# particle-logo-v2.net
KiCad netlist of a schematic drawn in EAGLE
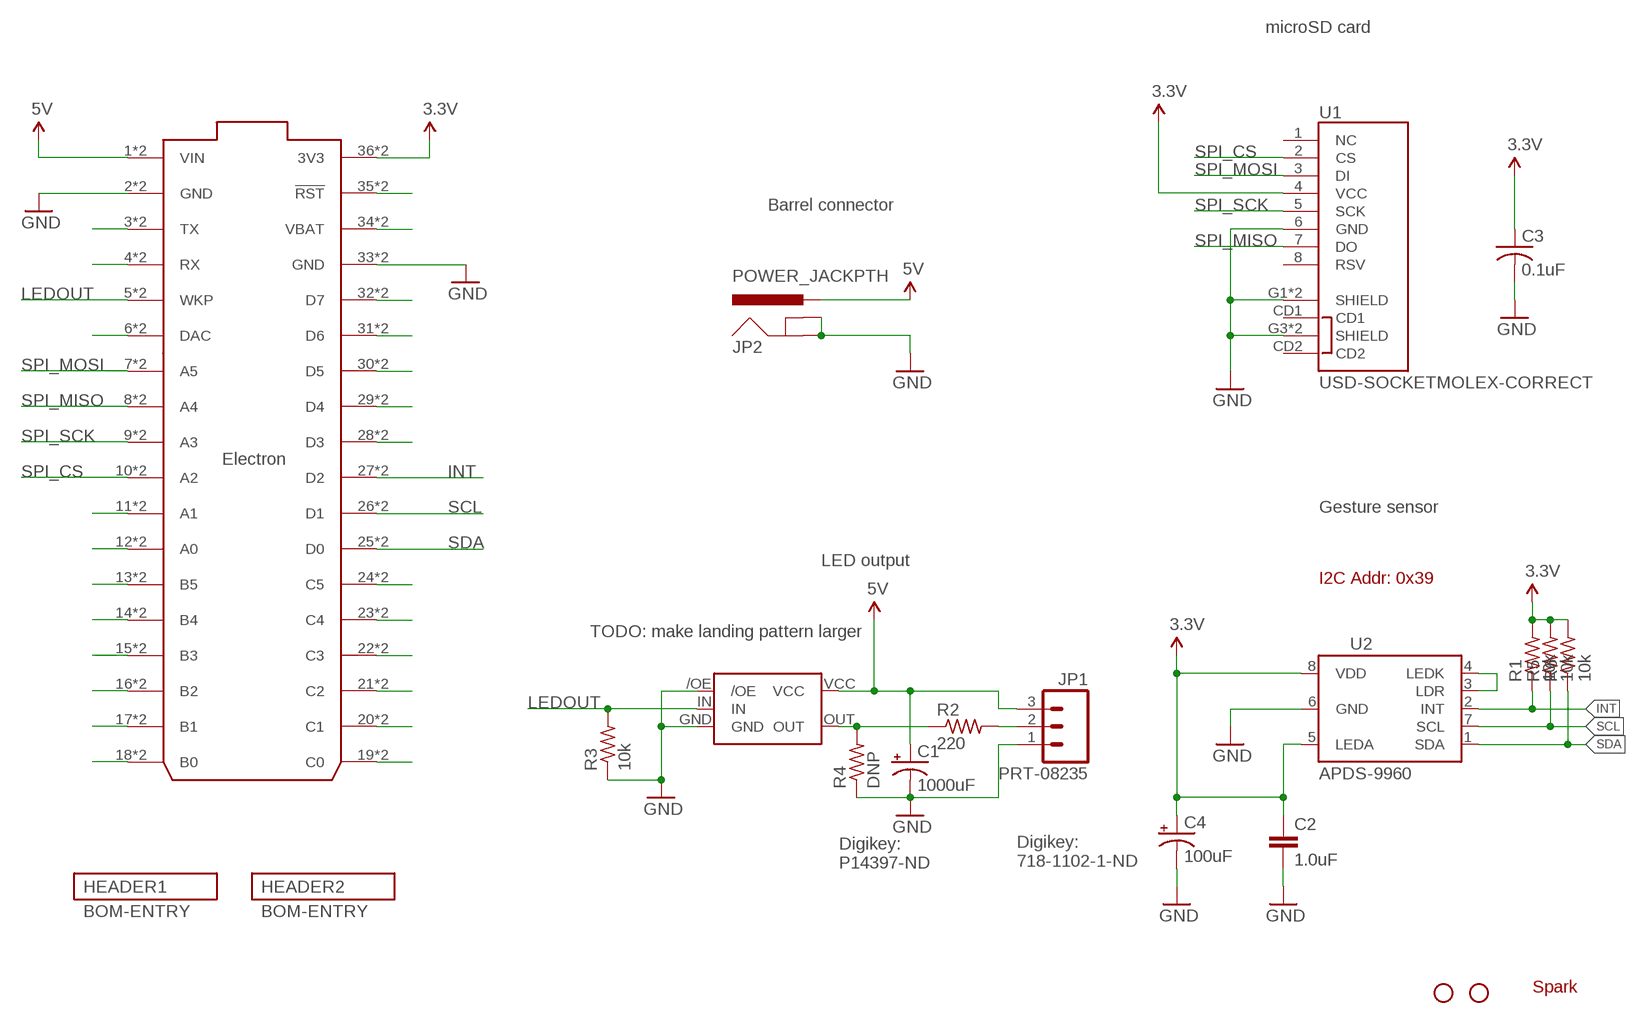
[diagram p0: schematic, sheet 1]

(export (version "E")
  (design (tool "Eeschema 10.0.6"))
  (components
    (comp (ref "C1")
      (value "1000uF")
      (footprint "eagle-import:CPOL-8MMX20MM-FLAT-MIR")
      (fields (field (name "PARTNO") "EEU-FR1C102L"))
      (libsource (lib "eagle-import") (part "CAP_POL8MMX20MM-FLAT-MIR"))
    )
    (comp (ref "C2")
      (value "1.0uF")
      (footprint "eagle-import:0603-CAP")
      (fields (field (name "PARTNO") "0603YD105KAT2A"))
      (libsource (lib "eagle-import") (part "1.0UF-16V-10%(0603)"))
    )
    (comp (ref "C3")
      (value "0.1uF")
      (footprint "eagle-import:C0603")
      (fields (field (name "PARTNO") "CC0603JRX7R7BB104"))
      (libsource (lib "eagle-import") (part "C-USC0603"))
    )
    (comp (ref "C4")
      (value "100uF")
      (footprint "eagle-import:EIA7343")
      (fields (field (name "PARTNO") "TAJD107K020RNJ"))
      (libsource (lib "eagle-import") (part "100UF-10V-10%(TANT)"))
    )
    (comp (ref "JP1")
      (value "PRT-08235")
      (footprint "eagle-import:SCREWTERMINAL-3.5MM-3")
      (libsource (lib "eagle-import") (part "M03SCREW"))
    )
    (comp (ref "JP2")
      (value "POWER_JACKPTH")
      (footprint "eagle-import:POWER_JACK_PTH")
      (libsource (lib "eagle-import") (part "POWER_JACKPTH"))
    )
    (comp (ref "R1")
      (value "10k")
      (footprint "eagle-import:R0603")
      (fields (field (name "PARTNO") "ERJ-3EKF1002V"))
      (libsource (lib "eagle-import") (part "R-US_R0603"))
    )
    (comp (ref "R2")
      (value "220")
      (footprint "eagle-import:R0603")
      (fields (field (name "PARTNO") "ERJ-3GEYJ221V"))
      (libsource (lib "eagle-import") (part "R-US_R0603"))
    )
    (comp (ref "R3")
      (value "10k")
      (footprint "eagle-import:R0603")
      (fields (field (name "PARTNO") "ERJ-3EKF1002V"))
      (libsource (lib "eagle-import") (part "R-US_R0603"))
    )
    (comp (ref "R4")
      (value "DNP")
      (footprint "eagle-import:R0603")
      (libsource (lib "eagle-import") (part "R-US_R0603"))
    )
    (comp (ref "R5")
      (value "10k")
      (footprint "eagle-import:R0603")
      (fields (field (name "PARTNO") "ERJ-3EKF1002V"))
      (libsource (lib "eagle-import") (part "R-US_R0603"))
    )
    (comp (ref "R6")
      (value "10k")
      (footprint "eagle-import:R0603")
      (fields (field (name "PARTNO") "ERJ-3EKF1002V"))
      (libsource (lib "eagle-import") (part "R-US_R0603"))
    )
    (comp (ref "STANDOFF1")
      (value "STAND-OFF")
      (footprint "eagle-import:STAND-OFF")
      (libsource (lib "eagle-import") (part "STAND-OFF"))
    )
    (comp (ref "STANDOFF2")
      (value "STAND-OFF")
      (footprint "eagle-import:STAND-OFF")
      (libsource (lib "eagle-import") (part "STAND-OFF"))
    )
    (comp (ref "U$1")
      (value "SPARK_LOGO2")
      (footprint "eagle-import:SPARK_LOGO2")
      (libsource (lib "eagle-import") (part "SPARK_LOGO2"))
    )
    (comp (ref "U1")
      (value "USD-SOCKETMOLEX-CORRECT")
      (footprint "eagle-import:MICRO-SD-MOLEX-CORRECT")
      (fields (field (name "PARTNO") "1040310811"))
      (libsource (lib "eagle-import") (part "USD-SOCKETMOLEX-CORRECT"))
    )
    (comp (ref "U2")
      (value "APDS-9960")
      (footprint "eagle-import:APDS-9960")
      (libsource (lib "eagle-import") (part "APDS-9960"))
    )
    (comp (ref "U3")
      (value "ELECTRON_WITH_EXTERNAL_HEADERS_NT")
      (footprint "eagle-import:ELECTRON_EXTERNAL_NT")
      (libsource (lib "eagle-import") (part "ELECTRON_WITH_EXTERNAL_HEADERS_NT"))
    )
    (comp (ref "U4")
      (value "NL17SZ125SOT553")
      (footprint "eagle-import:SOT-553")
      (fields (field (name "PARTNO") "NL17SZ125DTT1G"))
      (libsource (lib "eagle-import") (part "NL17SZ125SOT553"))
    )
  )
  (nets
    (net (code "1") (name "/LEDOUT") (class "Default")
      (node (ref "R3") (pin "2") (pinfunction "2_2") (pintype "passive"))
      (node (ref "U3") (pin "5") (pinfunction "WKP_5") (pintype "bidirectional"))
      (node (ref "U3") (pin "@5") (pinfunction "WKP_@5") (pintype "bidirectional"))
      (node (ref "U4") (pin "IN") (pinfunction "IN_IN") (pintype "bidirectional"))
    )
    (net (code "2") (name "/SPI_CS") (class "Default")
      (node (ref "U1") (pin "2") (pinfunction "CS_2") (pintype "bidirectional"))
      (node (ref "U3") (pin "10") (pinfunction "A2_10") (pintype "bidirectional"))
      (node (ref "U3") (pin "@10") (pinfunction "A2_@10") (pintype "bidirectional"))
    )
    (net (code "3") (name "/SPI_MISO") (class "Default")
      (node (ref "U1") (pin "7") (pinfunction "DO_7") (pintype "bidirectional"))
      (node (ref "U3") (pin "8") (pinfunction "A4_8") (pintype "bidirectional"))
      (node (ref "U3") (pin "@8") (pinfunction "A4_@8") (pintype "bidirectional"))
    )
    (net (code "4") (name "/SPI_MOSI") (class "Default")
      (node (ref "U1") (pin "3") (pinfunction "DI_3") (pintype "bidirectional"))
      (node (ref "U3") (pin "7") (pinfunction "A5_7") (pintype "bidirectional"))
      (node (ref "U3") (pin "@7") (pinfunction "A5_@7") (pintype "bidirectional"))
    )
    (net (code "5") (name "/SPI_SCK") (class "Default")
      (node (ref "U1") (pin "5") (pinfunction "SCK_5") (pintype "bidirectional"))
      (node (ref "U3") (pin "9") (pinfunction "A3_9") (pintype "bidirectional"))
      (node (ref "U3") (pin "@9") (pinfunction "A3_@9") (pintype "bidirectional"))
    )
    (net (code "6") (name "3.3V") (class "Default")
      (node (ref "C2") (pin "1") (pinfunction "1_1") (pintype "passive"))
      (node (ref "C3") (pin "1") (pinfunction "1_1") (pintype "passive"))
      (node (ref "C4") (pin "A") (pinfunction "+_A") (pintype "passive"))
      (node (ref "R1") (pin "2") (pinfunction "2_2") (pintype "passive"))
      (node (ref "R5") (pin "2") (pinfunction "2_2") (pintype "passive"))
      (node (ref "R6") (pin "2") (pinfunction "2_2") (pintype "passive"))
      (node (ref "U1") (pin "4") (pinfunction "VCC_4") (pintype "bidirectional"))
      (node (ref "U2") (pin "5") (pinfunction "LEDA_5") (pintype "bidirectional"))
      (node (ref "U2") (pin "8") (pinfunction "VDD_8") (pintype "bidirectional"))
      (node (ref "U3") (pin "36") (pinfunction "3V3_36") (pintype "power_in"))
      (node (ref "U3") (pin "@36") (pinfunction "3V3_@36") (pintype "power_in"))
    )
    (net (code "7") (name "5V") (class "Default")
      (node (ref "C1") (pin "2") (pinfunction "+_2") (pintype "passive"))
      (node (ref "JP1") (pin "3") (pinfunction "3_3") (pintype "passive"))
      (node (ref "JP2") (pin "PWR") (pinfunction "PWR_PWR") (pintype "bidirectional"))
      (node (ref "U3") (pin "1") (pinfunction "VIN_1") (pintype "power_in"))
      (node (ref "U3") (pin "@1") (pinfunction "VIN_@1") (pintype "power_in"))
      (node (ref "U4") (pin "VCC") (pinfunction "VCC_VCC") (pintype "bidirectional"))
    )
    (net (code "8") (name "GND") (class "Default")
      (node (ref "C1") (pin "1") (pinfunction "-_1") (pintype "passive"))
      (node (ref "C2") (pin "2") (pinfunction "2_2") (pintype "passive"))
      (node (ref "C3") (pin "2") (pinfunction "2_2") (pintype "passive"))
      (node (ref "C4") (pin "C") (pinfunction "-_C") (pintype "passive"))
      (node (ref "JP1") (pin "1") (pinfunction "1_1") (pintype "passive"))
      (node (ref "JP2") (pin "GND") (pinfunction "GND_GND") (pintype "bidirectional"))
      (node (ref "JP2") (pin "GNDBREAK") (pinfunction "GNDBREAK_GNDBREAK") (pintype "bidirectional"))
      (node (ref "R3") (pin "1") (pinfunction "1_1") (pintype "passive"))
      (node (ref "R4") (pin "1") (pinfunction "1_1") (pintype "passive"))
      (node (ref "U1") (pin "6") (pinfunction "GND_6") (pintype "bidirectional"))
      (node (ref "U1") (pin "G1") (pinfunction "SHIELD_G1") (pintype "bidirectional"))
      (node (ref "U1") (pin "G2") (pinfunction "SHIELD_G2") (pintype "bidirectional"))
      (node (ref "U1") (pin "G3") (pinfunction "SHIELD_G3") (pintype "bidirectional"))
      (node (ref "U1") (pin "G4") (pinfunction "SHIELD_G4") (pintype "bidirectional"))
      (node (ref "U2") (pin "6") (pinfunction "GND_6") (pintype "bidirectional"))
      (node (ref "U3") (pin "2") (pinfunction "GND_2") (pintype "power_in"))
      (node (ref "U3") (pin "33") (pinfunction "GND_33") (pintype "power_in"))
      (node (ref "U3") (pin "@2") (pinfunction "GND_@2") (pintype "power_in"))
      (node (ref "U3") (pin "@33") (pinfunction "GND_@33") (pintype "power_in"))
      (node (ref "U4") (pin "/OE") (pinfunction "/OE_/OE") (pintype "bidirectional"))
      (node (ref "U4") (pin "GND") (pinfunction "GND_GND") (pintype "bidirectional"))
    )
    (net (code "9") (name "INT") (class "Default")
      (node (ref "R1") (pin "1") (pinfunction "1_1") (pintype "passive"))
      (node (ref "U2") (pin "2") (pinfunction "INT_2") (pintype "bidirectional"))
      (node (ref "U3") (pin "27") (pinfunction "D2_27") (pintype "bidirectional"))
      (node (ref "U3") (pin "@27") (pinfunction "D2_@27") (pintype "bidirectional"))
    )
    (net (code "10") (name "Net-(JP1-Pad2)") (class "Default")
      (node (ref "JP1") (pin "2") (pinfunction "2_2") (pintype "passive"))
      (node (ref "R2") (pin "2") (pinfunction "2_2") (pintype "passive"))
    )
    (net (code "11") (name "Net-(R2-Pad1)") (class "Default")
      (node (ref "R2") (pin "1") (pinfunction "1_1") (pintype "passive"))
      (node (ref "R4") (pin "2") (pinfunction "2_2") (pintype "passive"))
      (node (ref "U4") (pin "OUT") (pinfunction "OUT_OUT") (pintype "bidirectional"))
    )
    (net (code "12") (name "Net-(U2-LDR)") (class "Default")
      (node (ref "U2") (pin "3") (pinfunction "LDR_3") (pintype "bidirectional"))
      (node (ref "U2") (pin "4") (pinfunction "LEDK_4") (pintype "bidirectional"))
    )
    (net (code "13") (name "Net-(U3-A0-Pad12)") (class "Default")
      (node (ref "U3") (pin "12") (pinfunction "A0_12") (pintype "bidirectional"))
      (node (ref "U3") (pin "@12") (pinfunction "A0_@12") (pintype "bidirectional"))
    )
    (net (code "14") (name "Net-(U3-A1-Pad11)") (class "Default")
      (node (ref "U3") (pin "11") (pinfunction "A1_11") (pintype "bidirectional"))
      (node (ref "U3") (pin "@11") (pinfunction "A1_@11") (pintype "bidirectional"))
    )
    (net (code "15") (name "Net-(U3-B0-Pad18)") (class "Default")
      (node (ref "U3") (pin "18") (pinfunction "B0_18") (pintype "bidirectional"))
      (node (ref "U3") (pin "@18") (pinfunction "B0_@18") (pintype "bidirectional"))
    )
    (net (code "16") (name "Net-(U3-B1-Pad17)") (class "Default")
      (node (ref "U3") (pin "17") (pinfunction "B1_17") (pintype "bidirectional"))
      (node (ref "U3") (pin "@17") (pinfunction "B1_@17") (pintype "bidirectional"))
    )
    (net (code "17") (name "Net-(U3-B2-Pad16)") (class "Default")
      (node (ref "U3") (pin "16") (pinfunction "B2_16") (pintype "bidirectional"))
      (node (ref "U3") (pin "@16") (pinfunction "B2_@16") (pintype "bidirectional"))
    )
    (net (code "18") (name "Net-(U3-B3-Pad15)") (class "Default")
      (node (ref "U3") (pin "15") (pinfunction "B3_15") (pintype "bidirectional"))
      (node (ref "U3") (pin "@15") (pinfunction "B3_@15") (pintype "bidirectional"))
    )
    (net (code "19") (name "Net-(U3-B4-Pad14)") (class "Default")
      (node (ref "U3") (pin "14") (pinfunction "B4_14") (pintype "bidirectional"))
      (node (ref "U3") (pin "@14") (pinfunction "B4_@14") (pintype "bidirectional"))
    )
    (net (code "20") (name "Net-(U3-B5-Pad13)") (class "Default")
      (node (ref "U3") (pin "13") (pinfunction "B5_13") (pintype "bidirectional"))
      (node (ref "U3") (pin "@13") (pinfunction "B5_@13") (pintype "bidirectional"))
    )
    (net (code "21") (name "Net-(U3-C0-Pad19)") (class "Default")
      (node (ref "U3") (pin "19") (pinfunction "C0_19") (pintype "bidirectional"))
      (node (ref "U3") (pin "@19") (pinfunction "C0_@19") (pintype "bidirectional"))
    )
    (net (code "22") (name "Net-(U3-C1-Pad20)") (class "Default")
      (node (ref "U3") (pin "20") (pinfunction "C1_20") (pintype "bidirectional"))
      (node (ref "U3") (pin "@20") (pinfunction "C1_@20") (pintype "bidirectional"))
    )
    (net (code "23") (name "Net-(U3-C2-Pad21)") (class "Default")
      (node (ref "U3") (pin "21") (pinfunction "C2_21") (pintype "bidirectional"))
      (node (ref "U3") (pin "@21") (pinfunction "C2_@21") (pintype "bidirectional"))
    )
    (net (code "24") (name "Net-(U3-C3-Pad22)") (class "Default")
      (node (ref "U3") (pin "22") (pinfunction "C3_22") (pintype "bidirectional"))
      (node (ref "U3") (pin "@22") (pinfunction "C3_@22") (pintype "bidirectional"))
    )
    (net (code "25") (name "Net-(U3-C4-Pad23)") (class "Default")
      (node (ref "U3") (pin "23") (pinfunction "C4_23") (pintype "bidirectional"))
      (node (ref "U3") (pin "@23") (pinfunction "C4_@23") (pintype "bidirectional"))
    )
    (net (code "26") (name "Net-(U3-C5-Pad24)") (class "Default")
      (node (ref "U3") (pin "24") (pinfunction "C5_24") (pintype "bidirectional"))
      (node (ref "U3") (pin "@24") (pinfunction "C5_@24") (pintype "bidirectional"))
    )
    (net (code "27") (name "Net-(U3-D3-Pad28)") (class "Default")
      (node (ref "U3") (pin "28") (pinfunction "D3_28") (pintype "bidirectional"))
      (node (ref "U3") (pin "@28") (pinfunction "D3_@28") (pintype "bidirectional"))
    )
    (net (code "28") (name "Net-(U3-D4-Pad29)") (class "Default")
      (node (ref "U3") (pin "29") (pinfunction "D4_29") (pintype "bidirectional"))
      (node (ref "U3") (pin "@29") (pinfunction "D4_@29") (pintype "bidirectional"))
    )
    (net (code "29") (name "Net-(U3-D5-Pad30)") (class "Default")
      (node (ref "U3") (pin "30") (pinfunction "D5_30") (pintype "bidirectional"))
      (node (ref "U3") (pin "@30") (pinfunction "D5_@30") (pintype "bidirectional"))
    )
    (net (code "30") (name "Net-(U3-D6-Pad31)") (class "Default")
      (node (ref "U3") (pin "31") (pinfunction "D6_31") (pintype "bidirectional"))
      (node (ref "U3") (pin "@31") (pinfunction "D6_@31") (pintype "bidirectional"))
    )
    (net (code "31") (name "Net-(U3-D7-Pad32)") (class "Default")
      (node (ref "U3") (pin "32") (pinfunction "D7_32") (pintype "bidirectional"))
      (node (ref "U3") (pin "@32") (pinfunction "D7_@32") (pintype "bidirectional"))
    )
    (net (code "32") (name "Net-(U3-DAC-Pad6)") (class "Default")
      (node (ref "U3") (pin "6") (pinfunction "DAC_6") (pintype "bidirectional"))
      (node (ref "U3") (pin "@6") (pinfunction "DAC_@6") (pintype "bidirectional"))
    )
    (net (code "33") (name "Net-(U3-RX-Pad4)") (class "Default")
      (node (ref "U3") (pin "4") (pinfunction "RX_4") (pintype "bidirectional"))
      (node (ref "U3") (pin "@4") (pinfunction "RX_@4") (pintype "bidirectional"))
    )
    (net (code "34") (name "Net-(U3-TX-Pad3)") (class "Default")
      (node (ref "U3") (pin "3") (pinfunction "TX_3") (pintype "bidirectional"))
      (node (ref "U3") (pin "@3") (pinfunction "TX_@3") (pintype "bidirectional"))
    )
    (net (code "35") (name "Net-(U3-VBAT-Pad34)") (class "Default")
      (node (ref "U3") (pin "34") (pinfunction "VBAT_34") (pintype "power_in"))
      (node (ref "U3") (pin "@34") (pinfunction "VBAT_@34") (pintype "power_in"))
    )
    (net (code "36") (name "Net-(U3-~{RST}-Pad35)") (class "Default")
      (node (ref "U3") (pin "35") (pinfunction "~{RST}_35") (pintype "bidirectional"))
      (node (ref "U3") (pin "@35") (pinfunction "~{RST}_@35") (pintype "bidirectional"))
    )
    (net (code "37") (name "SCL") (class "Default")
      (node (ref "R5") (pin "1") (pinfunction "1_1") (pintype "passive"))
      (node (ref "U2") (pin "7") (pinfunction "SCL_7") (pintype "bidirectional"))
      (node (ref "U3") (pin "26") (pinfunction "D1_26") (pintype "bidirectional"))
      (node (ref "U3") (pin "@26") (pinfunction "D1_@26") (pintype "bidirectional"))
    )
    (net (code "38") (name "SDA") (class "Default")
      (node (ref "R6") (pin "1") (pinfunction "1_1") (pintype "passive"))
      (node (ref "U2") (pin "1") (pinfunction "SDA_1") (pintype "bidirectional"))
      (node (ref "U3") (pin "25") (pinfunction "D0_25") (pintype "bidirectional"))
      (node (ref "U3") (pin "@25") (pinfunction "D0_@25") (pintype "bidirectional"))
    )
    (net (code "39") (name "unconnected-(U1-NC-Pad1)") (class "Default")
      (node (ref "U1") (pin "1") (pinfunction "NC_1") (pintype "bidirectional"))
    )
    (net (code "40") (name "unconnected-(U1-PadCD1)") (class "Default")
      (node (ref "U1") (pin "CD1") (pinfunction "CD1_CD1") (pintype "bidirectional"))
    )
    (net (code "41") (name "unconnected-(U1-PadCD2)") (class "Default")
      (node (ref "U1") (pin "CD2") (pinfunction "CD2_CD2") (pintype "bidirectional"))
    )
    (net (code "42") (name "unconnected-(U1-RSV-Pad8)") (class "Default")
      (node (ref "U1") (pin "8") (pinfunction "RSV_8") (pintype "bidirectional"))
    )
  )
)
